# microcontroller.net
KiCad netlist of a schematic drawn in Altium Designer
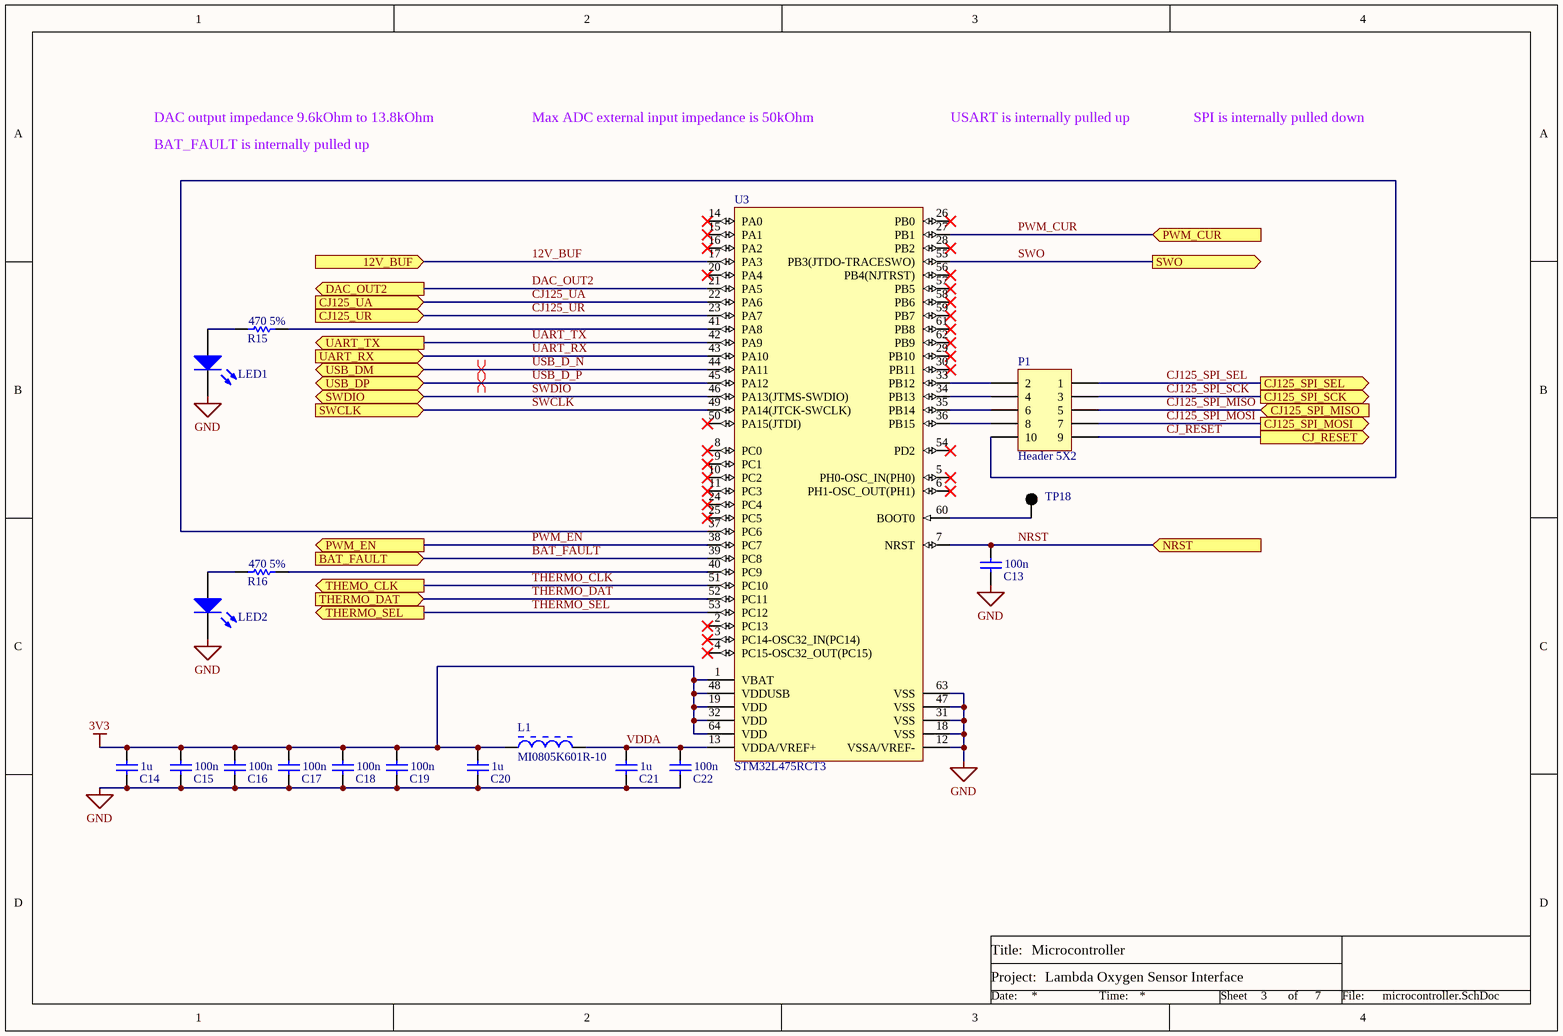
[diagram p0: microcontroller.SchDoc]

(export (version "E")
  (design (tool "Eeschema 10.0.6"))
  (components
    (comp (ref "C13")
      (value "100n")
      (footprint "0805")
      (description "Generic 0805 Capacitor")
      (libsource (lib "symbol_library") (part "C_0805"))
    )
    (comp (ref "C14")
      (value "1u")
      (footprint "1206")
      (description "Generic 1206 Capacitor")
      (libsource (lib "symbol_library") (part "C_1206"))
    )
    (comp (ref "C15")
      (value "100n")
      (footprint "0805")
      (description "Generic 0805 Capacitor")
      (libsource (lib "symbol_library") (part "C_0805"))
    )
    (comp (ref "C16")
      (value "100n")
      (footprint "0805")
      (description "Generic 0805 Capacitor")
      (libsource (lib "symbol_library") (part "C_0805"))
    )
    (comp (ref "C17")
      (value "100n")
      (footprint "0805")
      (description "Generic 0805 Capacitor")
      (libsource (lib "symbol_library") (part "C_0805"))
    )
    (comp (ref "C18")
      (value "100n")
      (footprint "0805")
      (description "Generic 0805 Capacitor")
      (libsource (lib "symbol_library") (part "C_0805"))
    )
    (comp (ref "C19")
      (value "100n")
      (footprint "0805")
      (description "Generic 0805 Capacitor")
      (libsource (lib "symbol_library") (part "C_0805"))
    )
    (comp (ref "C20")
      (value "1u")
      (footprint "1206")
      (description "Generic 1206 Capacitor")
      (libsource (lib "symbol_library") (part "C_1206"))
    )
    (comp (ref "C21")
      (value "1u")
      (footprint "1206")
      (description "Generic 1206 Capacitor")
      (libsource (lib "symbol_library") (part "C_1206"))
    )
    (comp (ref "C22")
      (value "100n")
      (footprint "0805")
      (description "Generic 0805 Capacitor")
      (libsource (lib "symbol_library") (part "C_0805"))
    )
    (comp (ref "L1")
      (value "MI0805K601R-10")
      (footprint "0805")
      (fields (field (name "MANUFACTURER") "Laird"))
      (libsource (lib "symbol_library") (part "MI0805K"))
    )
    (comp (ref "LED1")
      (value "150080SS75000")
      (footprint "0805_A")
      (description "SMD mono-color Chip LED, WL-SMCW, Super Red")
      (fields (field (name "MANUFACTURER") "Wuerth Elektronik"))
      (libsource (lib "symbol_library") (part "LED_0805"))
    )
    (comp (ref "LED2")
      (value "150080SS75000")
      (footprint "0805_A")
      (description "SMD mono-color Chip LED, WL-SMCW, Super Red")
      (fields (field (name "MANUFACTURER") "Wuerth Elektronik"))
      (libsource (lib "symbol_library") (part "LED_0805"))
    )
    (comp (ref "P1")
      (value "Header 5X2")
      (footprint "HDR2X5")
      (description "Header, 5-Pin, Dual row")
      (fields (field (name "PUBLISHER") "Altium Limited"))
      (libsource (lib "Miscellaneous Connectors") (part "Header 5X2"))
    )
    (comp (ref "R15")
      (value "470 5%")
      (footprint "0603")
      (description "Generic 0603 Resistor")
      (libsource (lib "symbol_library") (part "R_0603"))
    )
    (comp (ref "R16")
      (value "470 5%")
      (footprint "0603")
      (description "Generic 0603 Resistor")
      (libsource (lib "symbol_library") (part "R_0603"))
    )
    (comp (ref "TP18")
      (value "5001")
      (footprint "KSTN-5001")
      (description "Test Point, Black, 1-Pin THD, RoHS, Bulk")
      (fields (field (name "MANUFACTURER") "Keystone"))
      (libsource (lib "symbol_library") (part "TP5001"))
    )
    (comp (ref "U3")
      (value "STM32L475RCT3")
      (footprint "STM-LQFP64_L")
      (libsource (lib "symbol_library") (part "STM32L475RCT3"))
    )
  )
  (nets
    (net (code "1") (name "/12V_BUF") (class "Default")
      (node (ref "U3") (pin "17") (pinfunction "PA3_17") (pintype "bidirectional"))
    )
    (net (code "2") (name "/BAT_FAULT") (class "Default")
      (node (ref "U3") (pin "39") (pinfunction "PC8_39") (pintype "bidirectional"))
    )
    (net (code "3") (name "/CJ125_SPI_MISO") (class "Default")
      (node (ref "P1") (pin "5") (pinfunction "5_5") (pintype "passive"))
    )
    (net (code "4") (name "/CJ125_SPI_MOSI") (class "Default")
      (node (ref "P1") (pin "7") (pinfunction "7_7") (pintype "passive"))
    )
    (net (code "5") (name "/CJ125_SPI_SCK") (class "Default")
      (node (ref "P1") (pin "3") (pinfunction "3_3") (pintype "passive"))
    )
    (net (code "6") (name "/CJ125_SPI_SEL") (class "Default")
      (node (ref "P1") (pin "1") (pinfunction "1_1") (pintype "passive"))
    )
    (net (code "7") (name "/CJ125_UA") (class "Default")
      (node (ref "U3") (pin "22") (pinfunction "PA6_22") (pintype "bidirectional"))
    )
    (net (code "8") (name "/CJ125_UR") (class "Default")
      (node (ref "U3") (pin "23") (pinfunction "PA7_23") (pintype "bidirectional"))
    )
    (net (code "9") (name "/CJ_RESET") (class "Default")
      (node (ref "P1") (pin "9") (pinfunction "9_9") (pintype "passive"))
    )
    (net (code "10") (name "/DAC_OUT2") (class "Default")
      (node (ref "U3") (pin "21") (pinfunction "PA5_21") (pintype "bidirectional"))
    )
    (net (code "11") (name "/NRST") (class "Default")
      (node (ref "C13") (pin "2") (pinfunction "2_2") (pintype "passive"))
      (node (ref "U3") (pin "7") (pinfunction "NRST_7") (pintype "bidirectional"))
    )
    (net (code "12") (name "/PWM_CUR") (class "Default")
      (node (ref "U3") (pin "27") (pinfunction "PB1_27") (pintype "bidirectional"))
    )
    (net (code "13") (name "/PWM_EN") (class "Default")
      (node (ref "U3") (pin "38") (pinfunction "PC7_38") (pintype "bidirectional"))
    )
    (net (code "14") (name "/SWCLK") (class "Default")
      (node (ref "U3") (pin "49") (pinfunction "PA14(JTCK-SWCLK)_49") (pintype "bidirectional"))
    )
    (net (code "15") (name "/SWDIO") (class "Default")
      (node (ref "U3") (pin "46") (pinfunction "PA13(JTMS-SWDIO)_46") (pintype "bidirectional"))
    )
    (net (code "16") (name "/SWO") (class "Default")
      (node (ref "U3") (pin "55") (pinfunction "PB3(JTDO-TRACESWO)_55") (pintype "bidirectional"))
    )
    (net (code "17") (name "/THERMO_CLK") (class "Default")
      (node (ref "U3") (pin "51") (pinfunction "PC10_51") (pintype "bidirectional"))
    )
    (net (code "18") (name "/THERMO_DAT") (class "Default")
      (node (ref "U3") (pin "52") (pinfunction "PC11_52") (pintype "bidirectional"))
    )
    (net (code "19") (name "/THERMO_SEL") (class "Default")
      (node (ref "U3") (pin "53") (pinfunction "PC12_53") (pintype "bidirectional"))
    )
    (net (code "20") (name "/UART_RX") (class "Default")
      (node (ref "U3") (pin "43") (pinfunction "PA10_43") (pintype "bidirectional"))
    )
    (net (code "21") (name "/UART_TX") (class "Default")
      (node (ref "U3") (pin "42") (pinfunction "PA9_42") (pintype "bidirectional"))
    )
    (net (code "22") (name "/USB_D_N") (class "Default")
      (node (ref "U3") (pin "44") (pinfunction "PA11_44") (pintype "bidirectional"))
    )
    (net (code "23") (name "/USB_D_P") (class "Default")
      (node (ref "U3") (pin "45") (pinfunction "PA12_45") (pintype "bidirectional"))
    )
    (net (code "24") (name "/VDDA") (class "Default")
      (node (ref "C21") (pin "2") (pinfunction "2_2") (pintype "passive"))
      (node (ref "C22") (pin "2") (pinfunction "2_2") (pintype "passive"))
      (node (ref "L1") (pin "2") (pinfunction "2_2") (pintype "passive"))
      (node (ref "U3") (pin "13") (pinfunction "VDDA/VREF+_13") (pintype "power_in"))
    )
    (net (code "25") (name "3V3") (class "Default")
      (node (ref "C14") (pin "2") (pinfunction "2_2") (pintype "passive"))
      (node (ref "C15") (pin "2") (pinfunction "2_2") (pintype "passive"))
      (node (ref "C16") (pin "2") (pinfunction "2_2") (pintype "passive"))
      (node (ref "C17") (pin "2") (pinfunction "2_2") (pintype "passive"))
      (node (ref "C18") (pin "2") (pinfunction "2_2") (pintype "passive"))
      (node (ref "C19") (pin "2") (pinfunction "2_2") (pintype "passive"))
      (node (ref "C20") (pin "2") (pinfunction "2_2") (pintype "passive"))
      (node (ref "L1") (pin "1") (pinfunction "1_1") (pintype "passive"))
      (node (ref "U3") (pin "1") (pinfunction "VBAT_1") (pintype "power_in"))
      (node (ref "U3") (pin "19") (pinfunction "VDD_19") (pintype "power_in"))
      (node (ref "U3") (pin "32") (pinfunction "VDD_32") (pintype "power_in"))
      (node (ref "U3") (pin "48") (pinfunction "VDDUSB_48") (pintype "power_in"))
      (node (ref "U3") (pin "64") (pinfunction "VDD_64") (pintype "power_in"))
    )
    (net (code "26") (name "GND") (class "Default")
      (node (ref "C13") (pin "1") (pinfunction "1_1") (pintype "passive"))
      (node (ref "C14") (pin "1") (pinfunction "1_1") (pintype "passive"))
      (node (ref "C15") (pin "1") (pinfunction "1_1") (pintype "passive"))
      (node (ref "C16") (pin "1") (pinfunction "1_1") (pintype "passive"))
      (node (ref "C17") (pin "1") (pinfunction "1_1") (pintype "passive"))
      (node (ref "C18") (pin "1") (pinfunction "1_1") (pintype "passive"))
      (node (ref "C19") (pin "1") (pinfunction "1_1") (pintype "passive"))
      (node (ref "C20") (pin "1") (pinfunction "1_1") (pintype "passive"))
      (node (ref "C21") (pin "1") (pinfunction "1_1") (pintype "passive"))
      (node (ref "C22") (pin "1") (pinfunction "1_1") (pintype "passive"))
      (node (ref "LED1") (pin "1") (pinfunction "K_1") (pintype "passive"))
      (node (ref "LED2") (pin "1") (pinfunction "K_1") (pintype "passive"))
      (node (ref "U3") (pin "12") (pinfunction "VSSA/VREF-_12") (pintype "power_in"))
      (node (ref "U3") (pin "18") (pinfunction "VSS_18") (pintype "power_in"))
      (node (ref "U3") (pin "31") (pinfunction "VSS_31") (pintype "power_in"))
      (node (ref "U3") (pin "47") (pinfunction "VSS_47") (pintype "power_in"))
      (node (ref "U3") (pin "63") (pinfunction "VSS_63") (pintype "power_in"))
    )
    (net (code "27") (name "Net-(LED1-A)") (class "Default")
      (node (ref "LED1") (pin "2") (pinfunction "A_2") (pintype "passive"))
      (node (ref "R15") (pin "1") (pinfunction "1_1") (pintype "passive"))
    )
    (net (code "28") (name "Net-(LED2-A)") (class "Default")
      (node (ref "LED2") (pin "2") (pinfunction "A_2") (pintype "passive"))
      (node (ref "R16") (pin "1") (pinfunction "1_1") (pintype "passive"))
    )
    (net (code "29") (name "Net-(U3-BOOT0)") (class "Default")
      (node (ref "TP18") (pin "1") (pintype "passive"))
      (node (ref "U3") (pin "60") (pinfunction "BOOT0_60") (pintype "input"))
    )
    (net (code "30") (name "Net-(U3-PA8)") (class "Default")
      (node (ref "R15") (pin "2") (pinfunction "2_2") (pintype "passive"))
      (node (ref "U3") (pin "41") (pinfunction "PA8_41") (pintype "bidirectional"))
    )
    (net (code "31") (name "Net-(U3-PB12)") (class "Default")
      (node (ref "P1") (pin "2") (pinfunction "2_2") (pintype "passive"))
      (node (ref "U3") (pin "33") (pinfunction "PB12_33") (pintype "bidirectional"))
    )
    (net (code "32") (name "Net-(U3-PB13)") (class "Default")
      (node (ref "P1") (pin "4") (pinfunction "4_4") (pintype "passive"))
      (node (ref "U3") (pin "34") (pinfunction "PB13_34") (pintype "bidirectional"))
    )
    (net (code "33") (name "Net-(U3-PB14)") (class "Default")
      (node (ref "P1") (pin "6") (pinfunction "6_6") (pintype "passive"))
      (node (ref "U3") (pin "35") (pinfunction "PB14_35") (pintype "bidirectional"))
    )
    (net (code "34") (name "Net-(U3-PB15)") (class "Default")
      (node (ref "P1") (pin "8") (pinfunction "8_8") (pintype "passive"))
      (node (ref "U3") (pin "36") (pinfunction "PB15_36") (pintype "bidirectional"))
    )
    (net (code "35") (name "Net-(U3-PC6)") (class "Default")
      (node (ref "P1") (pin "10") (pinfunction "10_10") (pintype "passive"))
      (node (ref "U3") (pin "37") (pinfunction "PC6_37") (pintype "bidirectional"))
    )
    (net (code "36") (name "Net-(U3-PC9)") (class "Default")
      (node (ref "R16") (pin "2") (pinfunction "2_2") (pintype "passive"))
      (node (ref "U3") (pin "40") (pinfunction "PC9_40") (pintype "bidirectional"))
    )
    (net (code "37") (name "unconnected-(U3-PA0-Pad14)") (class "Default")
      (node (ref "U3") (pin "14") (pinfunction "PA0_14") (pintype "bidirectional+no_connect"))
    )
    (net (code "38") (name "unconnected-(U3-PA1-Pad15)") (class "Default")
      (node (ref "U3") (pin "15") (pinfunction "PA1_15") (pintype "bidirectional+no_connect"))
    )
    (net (code "39") (name "unconnected-(U3-PA2-Pad16)") (class "Default")
      (node (ref "U3") (pin "16") (pinfunction "PA2_16") (pintype "bidirectional+no_connect"))
    )
    (net (code "40") (name "unconnected-(U3-PA4-Pad20)") (class "Default")
      (node (ref "U3") (pin "20") (pinfunction "PA4_20") (pintype "bidirectional+no_connect"))
    )
    (net (code "41") (name "unconnected-(U3-PA15(JTDI)-Pad50)") (class "Default")
      (node (ref "U3") (pin "50") (pinfunction "PA15(JTDI)_50") (pintype "bidirectional+no_connect"))
    )
    (net (code "42") (name "unconnected-(U3-PB0-Pad26)") (class "Default")
      (node (ref "U3") (pin "26") (pinfunction "PB0_26") (pintype "bidirectional+no_connect"))
    )
    (net (code "43") (name "unconnected-(U3-PB2-Pad28)") (class "Default")
      (node (ref "U3") (pin "28") (pinfunction "PB2_28") (pintype "bidirectional+no_connect"))
    )
    (net (code "44") (name "unconnected-(U3-PB4(NJTRST)-Pad56)") (class "Default")
      (node (ref "U3") (pin "56") (pinfunction "PB4(NJTRST)_56") (pintype "bidirectional+no_connect"))
    )
    (net (code "45") (name "unconnected-(U3-PB5-Pad57)") (class "Default")
      (node (ref "U3") (pin "57") (pinfunction "PB5_57") (pintype "bidirectional+no_connect"))
    )
    (net (code "46") (name "unconnected-(U3-PB6-Pad58)") (class "Default")
      (node (ref "U3") (pin "58") (pinfunction "PB6_58") (pintype "bidirectional+no_connect"))
    )
    (net (code "47") (name "unconnected-(U3-PB7-Pad59)") (class "Default")
      (node (ref "U3") (pin "59") (pinfunction "PB7_59") (pintype "bidirectional+no_connect"))
    )
    (net (code "48") (name "unconnected-(U3-PB8-Pad61)") (class "Default")
      (node (ref "U3") (pin "61") (pinfunction "PB8_61") (pintype "bidirectional+no_connect"))
    )
    (net (code "49") (name "unconnected-(U3-PB9-Pad62)") (class "Default")
      (node (ref "U3") (pin "62") (pinfunction "PB9_62") (pintype "bidirectional+no_connect"))
    )
    (net (code "50") (name "unconnected-(U3-PB10-Pad29)") (class "Default")
      (node (ref "U3") (pin "29") (pinfunction "PB10_29") (pintype "bidirectional+no_connect"))
    )
    (net (code "51") (name "unconnected-(U3-PB11-Pad30)") (class "Default")
      (node (ref "U3") (pin "30") (pinfunction "PB11_30") (pintype "bidirectional+no_connect"))
    )
    (net (code "52") (name "unconnected-(U3-PC0-Pad8)") (class "Default")
      (node (ref "U3") (pin "8") (pinfunction "PC0_8") (pintype "bidirectional+no_connect"))
    )
    (net (code "53") (name "unconnected-(U3-PC1-Pad9)") (class "Default")
      (node (ref "U3") (pin "9") (pinfunction "PC1_9") (pintype "bidirectional+no_connect"))
    )
    (net (code "54") (name "unconnected-(U3-PC2-Pad10)") (class "Default")
      (node (ref "U3") (pin "10") (pinfunction "PC2_10") (pintype "bidirectional+no_connect"))
    )
    (net (code "55") (name "unconnected-(U3-PC3-Pad11)") (class "Default")
      (node (ref "U3") (pin "11") (pinfunction "PC3_11") (pintype "bidirectional+no_connect"))
    )
    (net (code "56") (name "unconnected-(U3-PC4-Pad24)") (class "Default")
      (node (ref "U3") (pin "24") (pinfunction "PC4_24") (pintype "bidirectional+no_connect"))
    )
    (net (code "57") (name "unconnected-(U3-PC5-Pad25)") (class "Default")
      (node (ref "U3") (pin "25") (pinfunction "PC5_25") (pintype "bidirectional+no_connect"))
    )
    (net (code "58") (name "unconnected-(U3-PC13-Pad2)") (class "Default")
      (node (ref "U3") (pin "2") (pinfunction "PC13_2") (pintype "bidirectional+no_connect"))
    )
    (net (code "59") (name "unconnected-(U3-PC14-OSC32_IN(PC14)-Pad3)") (class "Default")
      (node (ref "U3") (pin "3") (pinfunction "PC14-OSC32_IN(PC14)_3") (pintype "bidirectional+no_connect"))
    )
    (net (code "60") (name "unconnected-(U3-PC15-OSC32_OUT(PC15)-Pad4)") (class "Default")
      (node (ref "U3") (pin "4") (pinfunction "PC15-OSC32_OUT(PC15)_4") (pintype "bidirectional+no_connect"))
    )
    (net (code "61") (name "unconnected-(U3-PD2-Pad54)") (class "Default")
      (node (ref "U3") (pin "54") (pinfunction "PD2_54") (pintype "bidirectional+no_connect"))
    )
    (net (code "62") (name "unconnected-(U3-PH0-OSC_IN(PH0)-Pad5)") (class "Default")
      (node (ref "U3") (pin "5") (pinfunction "PH0-OSC_IN(PH0)_5") (pintype "bidirectional+no_connect"))
    )
    (net (code "63") (name "unconnected-(U3-PH1-OSC_OUT(PH1)-Pad6)") (class "Default")
      (node (ref "U3") (pin "6") (pinfunction "PH1-OSC_OUT(PH1)_6") (pintype "bidirectional+no_connect"))
    )
  )
)
